# dsd_badge.net
KiCad netlist of a schematic drawn in Altium Designer
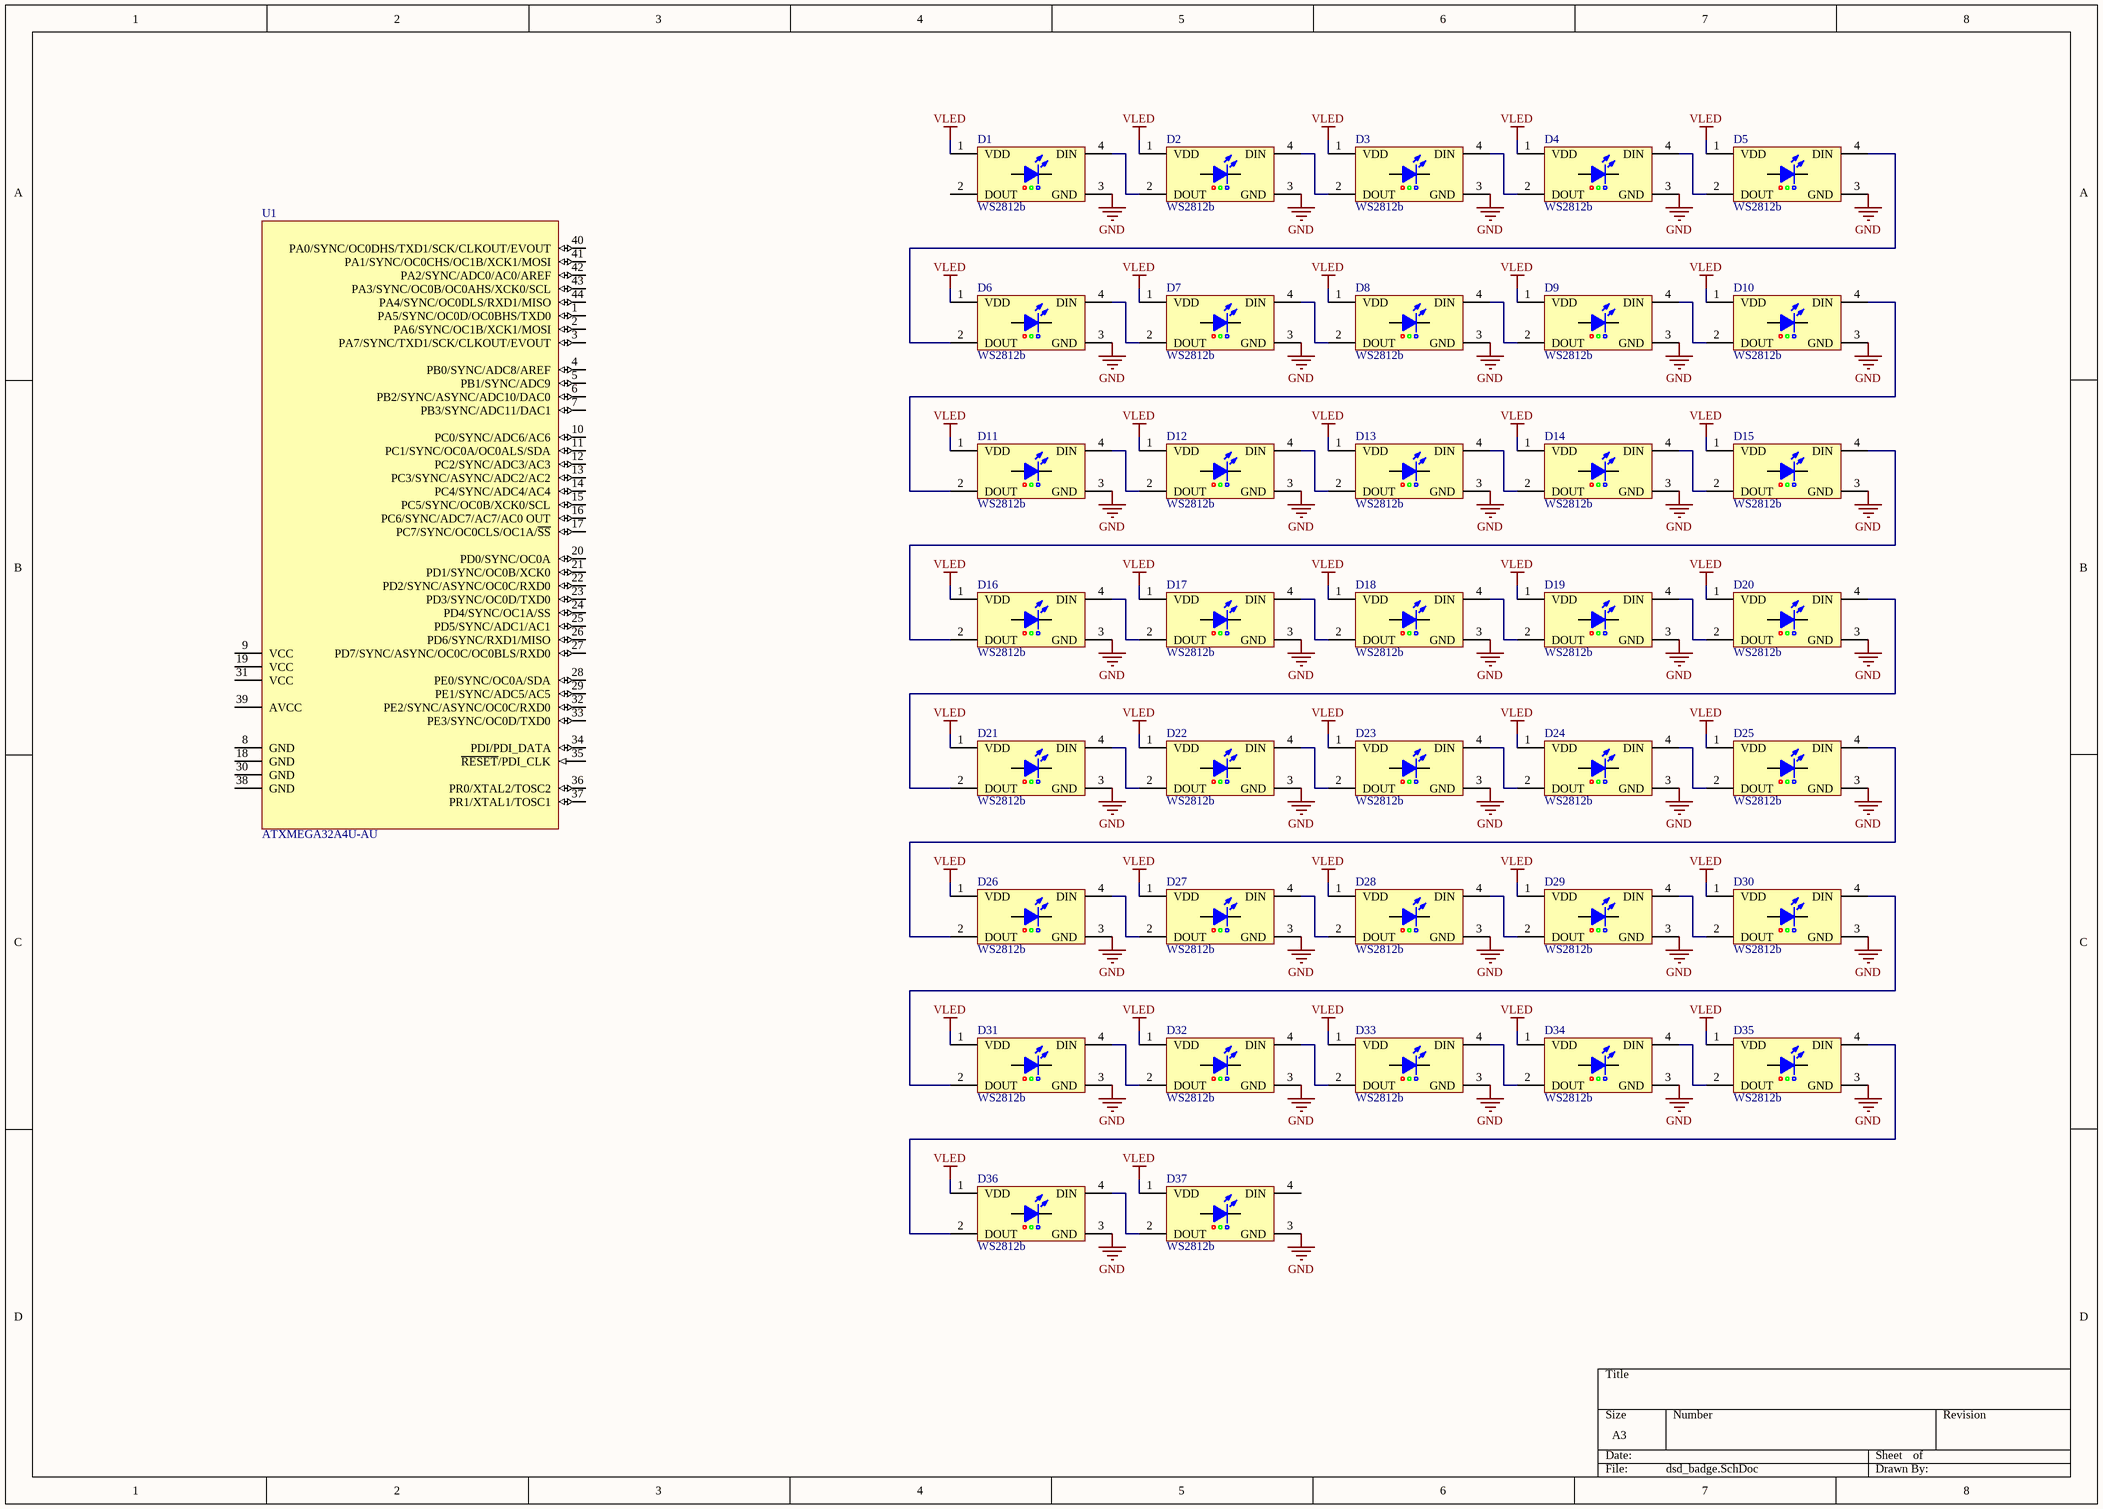
[diagram p0: dsd_badge.SchDoc]

(export (version "E")
  (design (tool "Eeschema 10.0.6"))
  (components
    (comp (ref "D1")
      (value "WS2812b")
      (footprint "WS2812B")
      (description "ADDRESS LED DISCR SER RGB 1=10")
      (fields
        (field (name "MANUFACTURER") "Adafruit Industries")
        (field (name "MANUFACTURER PART NUMBER") "1655")
      )
      (libsource (lib "General") (part "WS2812b"))
    )
    (comp (ref "D2")
      (value "WS2812b")
      (footprint "WS2812B")
      (description "ADDRESS LED DISCR SER RGB 1=10")
      (fields
        (field (name "MANUFACTURER") "Adafruit Industries")
        (field (name "MANUFACTURER PART NUMBER") "1655")
      )
      (libsource (lib "General") (part "WS2812b"))
    )
    (comp (ref "D3")
      (value "WS2812b")
      (footprint "WS2812B")
      (description "ADDRESS LED DISCR SER RGB 1=10")
      (fields
        (field (name "MANUFACTURER") "Adafruit Industries")
        (field (name "MANUFACTURER PART NUMBER") "1655")
      )
      (libsource (lib "General") (part "WS2812b"))
    )
    (comp (ref "D4")
      (value "WS2812b")
      (footprint "WS2812B")
      (description "ADDRESS LED DISCR SER RGB 1=10")
      (fields
        (field (name "MANUFACTURER") "Adafruit Industries")
        (field (name "MANUFACTURER PART NUMBER") "1655")
      )
      (libsource (lib "General") (part "WS2812b"))
    )
    (comp (ref "D5")
      (value "WS2812b")
      (footprint "WS2812B")
      (description "ADDRESS LED DISCR SER RGB 1=10")
      (fields
        (field (name "MANUFACTURER") "Adafruit Industries")
        (field (name "MANUFACTURER PART NUMBER") "1655")
      )
      (libsource (lib "General") (part "WS2812b"))
    )
    (comp (ref "D6")
      (value "WS2812b")
      (footprint "WS2812B")
      (description "ADDRESS LED DISCR SER RGB 1=10")
      (fields
        (field (name "MANUFACTURER") "Adafruit Industries")
        (field (name "MANUFACTURER PART NUMBER") "1655")
      )
      (libsource (lib "General") (part "WS2812b"))
    )
    (comp (ref "D7")
      (value "WS2812b")
      (footprint "WS2812B")
      (description "ADDRESS LED DISCR SER RGB 1=10")
      (fields
        (field (name "MANUFACTURER") "Adafruit Industries")
        (field (name "MANUFACTURER PART NUMBER") "1655")
      )
      (libsource (lib "General") (part "WS2812b"))
    )
    (comp (ref "D8")
      (value "WS2812b")
      (footprint "WS2812B")
      (description "ADDRESS LED DISCR SER RGB 1=10")
      (fields
        (field (name "MANUFACTURER") "Adafruit Industries")
        (field (name "MANUFACTURER PART NUMBER") "1655")
      )
      (libsource (lib "General") (part "WS2812b"))
    )
    (comp (ref "D9")
      (value "WS2812b")
      (footprint "WS2812B")
      (description "ADDRESS LED DISCR SER RGB 1=10")
      (fields
        (field (name "MANUFACTURER") "Adafruit Industries")
        (field (name "MANUFACTURER PART NUMBER") "1655")
      )
      (libsource (lib "General") (part "WS2812b"))
    )
    (comp (ref "D10")
      (value "WS2812b")
      (footprint "WS2812B")
      (description "ADDRESS LED DISCR SER RGB 1=10")
      (fields
        (field (name "MANUFACTURER") "Adafruit Industries")
        (field (name "MANUFACTURER PART NUMBER") "1655")
      )
      (libsource (lib "General") (part "WS2812b"))
    )
    (comp (ref "D11")
      (value "WS2812b")
      (footprint "WS2812B")
      (description "ADDRESS LED DISCR SER RGB 1=10")
      (fields
        (field (name "MANUFACTURER") "Adafruit Industries")
        (field (name "MANUFACTURER PART NUMBER") "1655")
      )
      (libsource (lib "General") (part "WS2812b"))
    )
    (comp (ref "D12")
      (value "WS2812b")
      (footprint "WS2812B")
      (description "ADDRESS LED DISCR SER RGB 1=10")
      (fields
        (field (name "MANUFACTURER") "Adafruit Industries")
        (field (name "MANUFACTURER PART NUMBER") "1655")
      )
      (libsource (lib "General") (part "WS2812b"))
    )
    (comp (ref "D13")
      (value "WS2812b")
      (footprint "WS2812B")
      (description "ADDRESS LED DISCR SER RGB 1=10")
      (fields
        (field (name "MANUFACTURER") "Adafruit Industries")
        (field (name "MANUFACTURER PART NUMBER") "1655")
      )
      (libsource (lib "General") (part "WS2812b"))
    )
    (comp (ref "D14")
      (value "WS2812b")
      (footprint "WS2812B")
      (description "ADDRESS LED DISCR SER RGB 1=10")
      (fields
        (field (name "MANUFACTURER") "Adafruit Industries")
        (field (name "MANUFACTURER PART NUMBER") "1655")
      )
      (libsource (lib "General") (part "WS2812b"))
    )
    (comp (ref "D15")
      (value "WS2812b")
      (footprint "WS2812B")
      (description "ADDRESS LED DISCR SER RGB 1=10")
      (fields
        (field (name "MANUFACTURER") "Adafruit Industries")
        (field (name "MANUFACTURER PART NUMBER") "1655")
      )
      (libsource (lib "General") (part "WS2812b"))
    )
    (comp (ref "D16")
      (value "WS2812b")
      (footprint "WS2812B")
      (description "ADDRESS LED DISCR SER RGB 1=10")
      (fields
        (field (name "MANUFACTURER") "Adafruit Industries")
        (field (name "MANUFACTURER PART NUMBER") "1655")
      )
      (libsource (lib "General") (part "WS2812b"))
    )
    (comp (ref "D17")
      (value "WS2812b")
      (footprint "WS2812B")
      (description "ADDRESS LED DISCR SER RGB 1=10")
      (fields
        (field (name "MANUFACTURER") "Adafruit Industries")
        (field (name "MANUFACTURER PART NUMBER") "1655")
      )
      (libsource (lib "General") (part "WS2812b"))
    )
    (comp (ref "D18")
      (value "WS2812b")
      (footprint "WS2812B")
      (description "ADDRESS LED DISCR SER RGB 1=10")
      (fields
        (field (name "MANUFACTURER") "Adafruit Industries")
        (field (name "MANUFACTURER PART NUMBER") "1655")
      )
      (libsource (lib "General") (part "WS2812b"))
    )
    (comp (ref "D19")
      (value "WS2812b")
      (footprint "WS2812B")
      (description "ADDRESS LED DISCR SER RGB 1=10")
      (fields
        (field (name "MANUFACTURER") "Adafruit Industries")
        (field (name "MANUFACTURER PART NUMBER") "1655")
      )
      (libsource (lib "General") (part "WS2812b"))
    )
    (comp (ref "D20")
      (value "WS2812b")
      (footprint "WS2812B")
      (description "ADDRESS LED DISCR SER RGB 1=10")
      (fields
        (field (name "MANUFACTURER") "Adafruit Industries")
        (field (name "MANUFACTURER PART NUMBER") "1655")
      )
      (libsource (lib "General") (part "WS2812b"))
    )
    (comp (ref "D21")
      (value "WS2812b")
      (footprint "WS2812B")
      (description "ADDRESS LED DISCR SER RGB 1=10")
      (fields
        (field (name "MANUFACTURER") "Adafruit Industries")
        (field (name "MANUFACTURER PART NUMBER") "1655")
      )
      (libsource (lib "General") (part "WS2812b"))
    )
    (comp (ref "D22")
      (value "WS2812b")
      (footprint "WS2812B")
      (description "ADDRESS LED DISCR SER RGB 1=10")
      (fields
        (field (name "MANUFACTURER") "Adafruit Industries")
        (field (name "MANUFACTURER PART NUMBER") "1655")
      )
      (libsource (lib "General") (part "WS2812b"))
    )
    (comp (ref "D23")
      (value "WS2812b")
      (footprint "WS2812B")
      (description "ADDRESS LED DISCR SER RGB 1=10")
      (fields
        (field (name "MANUFACTURER") "Adafruit Industries")
        (field (name "MANUFACTURER PART NUMBER") "1655")
      )
      (libsource (lib "General") (part "WS2812b"))
    )
    (comp (ref "D24")
      (value "WS2812b")
      (footprint "WS2812B")
      (description "ADDRESS LED DISCR SER RGB 1=10")
      (fields
        (field (name "MANUFACTURER") "Adafruit Industries")
        (field (name "MANUFACTURER PART NUMBER") "1655")
      )
      (libsource (lib "General") (part "WS2812b"))
    )
    (comp (ref "D25")
      (value "WS2812b")
      (footprint "WS2812B")
      (description "ADDRESS LED DISCR SER RGB 1=10")
      (fields
        (field (name "MANUFACTURER") "Adafruit Industries")
        (field (name "MANUFACTURER PART NUMBER") "1655")
      )
      (libsource (lib "General") (part "WS2812b"))
    )
    (comp (ref "D26")
      (value "WS2812b")
      (footprint "WS2812B")
      (description "ADDRESS LED DISCR SER RGB 1=10")
      (fields
        (field (name "MANUFACTURER") "Adafruit Industries")
        (field (name "MANUFACTURER PART NUMBER") "1655")
      )
      (libsource (lib "General") (part "WS2812b"))
    )
    (comp (ref "D27")
      (value "WS2812b")
      (footprint "WS2812B")
      (description "ADDRESS LED DISCR SER RGB 1=10")
      (fields
        (field (name "MANUFACTURER") "Adafruit Industries")
        (field (name "MANUFACTURER PART NUMBER") "1655")
      )
      (libsource (lib "General") (part "WS2812b"))
    )
    (comp (ref "D28")
      (value "WS2812b")
      (footprint "WS2812B")
      (description "ADDRESS LED DISCR SER RGB 1=10")
      (fields
        (field (name "MANUFACTURER") "Adafruit Industries")
        (field (name "MANUFACTURER PART NUMBER") "1655")
      )
      (libsource (lib "General") (part "WS2812b"))
    )
    (comp (ref "D29")
      (value "WS2812b")
      (footprint "WS2812B")
      (description "ADDRESS LED DISCR SER RGB 1=10")
      (fields
        (field (name "MANUFACTURER") "Adafruit Industries")
        (field (name "MANUFACTURER PART NUMBER") "1655")
      )
      (libsource (lib "General") (part "WS2812b"))
    )
    (comp (ref "D30")
      (value "WS2812b")
      (footprint "WS2812B")
      (description "ADDRESS LED DISCR SER RGB 1=10")
      (fields
        (field (name "MANUFACTURER") "Adafruit Industries")
        (field (name "MANUFACTURER PART NUMBER") "1655")
      )
      (libsource (lib "General") (part "WS2812b"))
    )
    (comp (ref "D31")
      (value "WS2812b")
      (footprint "WS2812B")
      (description "ADDRESS LED DISCR SER RGB 1=10")
      (fields
        (field (name "MANUFACTURER") "Adafruit Industries")
        (field (name "MANUFACTURER PART NUMBER") "1655")
      )
      (libsource (lib "General") (part "WS2812b"))
    )
    (comp (ref "D32")
      (value "WS2812b")
      (footprint "WS2812B")
      (description "ADDRESS LED DISCR SER RGB 1=10")
      (fields
        (field (name "MANUFACTURER") "Adafruit Industries")
        (field (name "MANUFACTURER PART NUMBER") "1655")
      )
      (libsource (lib "General") (part "WS2812b"))
    )
    (comp (ref "D33")
      (value "WS2812b")
      (footprint "WS2812B")
      (description "ADDRESS LED DISCR SER RGB 1=10")
      (fields
        (field (name "MANUFACTURER") "Adafruit Industries")
        (field (name "MANUFACTURER PART NUMBER") "1655")
      )
      (libsource (lib "General") (part "WS2812b"))
    )
    (comp (ref "D34")
      (value "WS2812b")
      (footprint "WS2812B")
      (description "ADDRESS LED DISCR SER RGB 1=10")
      (fields
        (field (name "MANUFACTURER") "Adafruit Industries")
        (field (name "MANUFACTURER PART NUMBER") "1655")
      )
      (libsource (lib "General") (part "WS2812b"))
    )
    (comp (ref "D35")
      (value "WS2812b")
      (footprint "WS2812B")
      (description "ADDRESS LED DISCR SER RGB 1=10")
      (fields
        (field (name "MANUFACTURER") "Adafruit Industries")
        (field (name "MANUFACTURER PART NUMBER") "1655")
      )
      (libsource (lib "General") (part "WS2812b"))
    )
    (comp (ref "D36")
      (value "WS2812b")
      (footprint "WS2812B")
      (description "ADDRESS LED DISCR SER RGB 1=10")
      (fields
        (field (name "MANUFACTURER") "Adafruit Industries")
        (field (name "MANUFACTURER PART NUMBER") "1655")
      )
      (libsource (lib "General") (part "WS2812b"))
    )
    (comp (ref "D37")
      (value "WS2812b")
      (footprint "WS2812B")
      (description "ADDRESS LED DISCR SER RGB 1=10")
      (fields
        (field (name "MANUFACTURER") "Adafruit Industries")
        (field (name "MANUFACTURER PART NUMBER") "1655")
      )
      (libsource (lib "General") (part "WS2812b"))
    )
    (comp (ref "U1")
      (value "ATXMEGA32A4U-AU")
      (footprint "44A_L")
      (description "IC MCU 8BIT 32KB FLASH 44TQFP")
      (fields (field (name "MANUFACTURER") "Atmel"))
      (libsource (lib "General") (part "ATXMEGA32A4U-AU"))
    )
  )
  (nets
    (net (code "1") (name "GND") (class "Default")
      (node (ref "D1") (pin "3") (pinfunction "GND_3") (pintype "passive"))
      (node (ref "D10") (pin "3") (pinfunction "GND_3") (pintype "passive"))
      (node (ref "D11") (pin "3") (pinfunction "GND_3") (pintype "passive"))
      (node (ref "D12") (pin "3") (pinfunction "GND_3") (pintype "passive"))
      (node (ref "D13") (pin "3") (pinfunction "GND_3") (pintype "passive"))
      (node (ref "D14") (pin "3") (pinfunction "GND_3") (pintype "passive"))
      (node (ref "D15") (pin "3") (pinfunction "GND_3") (pintype "passive"))
      (node (ref "D16") (pin "3") (pinfunction "GND_3") (pintype "passive"))
      (node (ref "D17") (pin "3") (pinfunction "GND_3") (pintype "passive"))
      (node (ref "D18") (pin "3") (pinfunction "GND_3") (pintype "passive"))
      (node (ref "D19") (pin "3") (pinfunction "GND_3") (pintype "passive"))
      (node (ref "D2") (pin "3") (pinfunction "GND_3") (pintype "passive"))
      (node (ref "D20") (pin "3") (pinfunction "GND_3") (pintype "passive"))
      (node (ref "D21") (pin "3") (pinfunction "GND_3") (pintype "passive"))
      (node (ref "D22") (pin "3") (pinfunction "GND_3") (pintype "passive"))
      (node (ref "D23") (pin "3") (pinfunction "GND_3") (pintype "passive"))
      (node (ref "D24") (pin "3") (pinfunction "GND_3") (pintype "passive"))
      (node (ref "D25") (pin "3") (pinfunction "GND_3") (pintype "passive"))
      (node (ref "D26") (pin "3") (pinfunction "GND_3") (pintype "passive"))
      (node (ref "D27") (pin "3") (pinfunction "GND_3") (pintype "passive"))
      (node (ref "D28") (pin "3") (pinfunction "GND_3") (pintype "passive"))
      (node (ref "D29") (pin "3") (pinfunction "GND_3") (pintype "passive"))
      (node (ref "D3") (pin "3") (pinfunction "GND_3") (pintype "passive"))
      (node (ref "D30") (pin "3") (pinfunction "GND_3") (pintype "passive"))
      (node (ref "D31") (pin "3") (pinfunction "GND_3") (pintype "passive"))
      (node (ref "D32") (pin "3") (pinfunction "GND_3") (pintype "passive"))
      (node (ref "D33") (pin "3") (pinfunction "GND_3") (pintype "passive"))
      (node (ref "D34") (pin "3") (pinfunction "GND_3") (pintype "passive"))
      (node (ref "D35") (pin "3") (pinfunction "GND_3") (pintype "passive"))
      (node (ref "D36") (pin "3") (pinfunction "GND_3") (pintype "passive"))
      (node (ref "D37") (pin "3") (pinfunction "GND_3") (pintype "passive"))
      (node (ref "D4") (pin "3") (pinfunction "GND_3") (pintype "passive"))
      (node (ref "D5") (pin "3") (pinfunction "GND_3") (pintype "passive"))
      (node (ref "D6") (pin "3") (pinfunction "GND_3") (pintype "passive"))
      (node (ref "D7") (pin "3") (pinfunction "GND_3") (pintype "passive"))
      (node (ref "D8") (pin "3") (pinfunction "GND_3") (pintype "passive"))
      (node (ref "D9") (pin "3") (pinfunction "GND_3") (pintype "passive"))
    )
    (net (code "2") (name "Net-(D1-DIN)") (class "Default")
      (node (ref "D1") (pin "4") (pinfunction "DIN_4") (pintype "passive"))
      (node (ref "D2") (pin "2") (pinfunction "DOUT_2") (pintype "passive"))
    )
    (net (code "3") (name "Net-(D2-DIN)") (class "Default")
      (node (ref "D2") (pin "4") (pinfunction "DIN_4") (pintype "passive"))
      (node (ref "D3") (pin "2") (pinfunction "DOUT_2") (pintype "passive"))
    )
    (net (code "4") (name "Net-(D3-DIN)") (class "Default")
      (node (ref "D3") (pin "4") (pinfunction "DIN_4") (pintype "passive"))
      (node (ref "D4") (pin "2") (pinfunction "DOUT_2") (pintype "passive"))
    )
    (net (code "5") (name "Net-(D4-DIN)") (class "Default")
      (node (ref "D4") (pin "4") (pinfunction "DIN_4") (pintype "passive"))
      (node (ref "D5") (pin "2") (pinfunction "DOUT_2") (pintype "passive"))
    )
    (net (code "6") (name "Net-(D5-DIN)") (class "Default")
      (node (ref "D5") (pin "4") (pinfunction "DIN_4") (pintype "passive"))
      (node (ref "D6") (pin "2") (pinfunction "DOUT_2") (pintype "passive"))
    )
    (net (code "7") (name "Net-(D6-DIN)") (class "Default")
      (node (ref "D6") (pin "4") (pinfunction "DIN_4") (pintype "passive"))
      (node (ref "D7") (pin "2") (pinfunction "DOUT_2") (pintype "passive"))
    )
    (net (code "8") (name "Net-(D7-DIN)") (class "Default")
      (node (ref "D7") (pin "4") (pinfunction "DIN_4") (pintype "passive"))
      (node (ref "D8") (pin "2") (pinfunction "DOUT_2") (pintype "passive"))
    )
    (net (code "9") (name "Net-(D8-DIN)") (class "Default")
      (node (ref "D8") (pin "4") (pinfunction "DIN_4") (pintype "passive"))
      (node (ref "D9") (pin "2") (pinfunction "DOUT_2") (pintype "passive"))
    )
    (net (code "10") (name "Net-(D10-DIN)") (class "Default")
      (node (ref "D10") (pin "4") (pinfunction "DIN_4") (pintype "passive"))
      (node (ref "D11") (pin "2") (pinfunction "DOUT_2") (pintype "passive"))
    )
    (net (code "11") (name "Net-(D10-DOUT)") (class "Default")
      (node (ref "D10") (pin "2") (pinfunction "DOUT_2") (pintype "passive"))
      (node (ref "D9") (pin "4") (pinfunction "DIN_4") (pintype "passive"))
    )
    (net (code "12") (name "Net-(D11-DIN)") (class "Default")
      (node (ref "D11") (pin "4") (pinfunction "DIN_4") (pintype "passive"))
      (node (ref "D12") (pin "2") (pinfunction "DOUT_2") (pintype "passive"))
    )
    (net (code "13") (name "Net-(D12-DIN)") (class "Default")
      (node (ref "D12") (pin "4") (pinfunction "DIN_4") (pintype "passive"))
      (node (ref "D13") (pin "2") (pinfunction "DOUT_2") (pintype "passive"))
    )
    (net (code "14") (name "Net-(D13-DIN)") (class "Default")
      (node (ref "D13") (pin "4") (pinfunction "DIN_4") (pintype "passive"))
      (node (ref "D14") (pin "2") (pinfunction "DOUT_2") (pintype "passive"))
    )
    (net (code "15") (name "Net-(D14-DIN)") (class "Default")
      (node (ref "D14") (pin "4") (pinfunction "DIN_4") (pintype "passive"))
      (node (ref "D15") (pin "2") (pinfunction "DOUT_2") (pintype "passive"))
    )
    (net (code "16") (name "Net-(D15-DIN)") (class "Default")
      (node (ref "D15") (pin "4") (pinfunction "DIN_4") (pintype "passive"))
      (node (ref "D16") (pin "2") (pinfunction "DOUT_2") (pintype "passive"))
    )
    (net (code "17") (name "Net-(D16-DIN)") (class "Default")
      (node (ref "D16") (pin "4") (pinfunction "DIN_4") (pintype "passive"))
      (node (ref "D17") (pin "2") (pinfunction "DOUT_2") (pintype "passive"))
    )
    (net (code "18") (name "Net-(D17-DIN)") (class "Default")
      (node (ref "D17") (pin "4") (pinfunction "DIN_4") (pintype "passive"))
      (node (ref "D18") (pin "2") (pinfunction "DOUT_2") (pintype "passive"))
    )
    (net (code "19") (name "Net-(D18-DIN)") (class "Default")
      (node (ref "D18") (pin "4") (pinfunction "DIN_4") (pintype "passive"))
      (node (ref "D19") (pin "2") (pinfunction "DOUT_2") (pintype "passive"))
    )
    (net (code "20") (name "Net-(D19-DIN)") (class "Default")
      (node (ref "D19") (pin "4") (pinfunction "DIN_4") (pintype "passive"))
      (node (ref "D20") (pin "2") (pinfunction "DOUT_2") (pintype "passive"))
    )
    (net (code "21") (name "Net-(D20-DIN)") (class "Default")
      (node (ref "D20") (pin "4") (pinfunction "DIN_4") (pintype "passive"))
      (node (ref "D21") (pin "2") (pinfunction "DOUT_2") (pintype "passive"))
    )
    (net (code "22") (name "Net-(D21-DIN)") (class "Default")
      (node (ref "D21") (pin "4") (pinfunction "DIN_4") (pintype "passive"))
      (node (ref "D22") (pin "2") (pinfunction "DOUT_2") (pintype "passive"))
    )
    (net (code "23") (name "Net-(D22-DIN)") (class "Default")
      (node (ref "D22") (pin "4") (pinfunction "DIN_4") (pintype "passive"))
      (node (ref "D23") (pin "2") (pinfunction "DOUT_2") (pintype "passive"))
    )
    (net (code "24") (name "Net-(D23-DIN)") (class "Default")
      (node (ref "D23") (pin "4") (pinfunction "DIN_4") (pintype "passive"))
      (node (ref "D24") (pin "2") (pinfunction "DOUT_2") (pintype "passive"))
    )
    (net (code "25") (name "Net-(D24-DIN)") (class "Default")
      (node (ref "D24") (pin "4") (pinfunction "DIN_4") (pintype "passive"))
      (node (ref "D25") (pin "2") (pinfunction "DOUT_2") (pintype "passive"))
    )
    (net (code "26") (name "Net-(D25-DIN)") (class "Default")
      (node (ref "D25") (pin "4") (pinfunction "DIN_4") (pintype "passive"))
      (node (ref "D26") (pin "2") (pinfunction "DOUT_2") (pintype "passive"))
    )
    (net (code "27") (name "Net-(D26-DIN)") (class "Default")
      (node (ref "D26") (pin "4") (pinfunction "DIN_4") (pintype "passive"))
      (node (ref "D27") (pin "2") (pinfunction "DOUT_2") (pintype "passive"))
    )
    (net (code "28") (name "Net-(D27-DIN)") (class "Default")
      (node (ref "D27") (pin "4") (pinfunction "DIN_4") (pintype "passive"))
      (node (ref "D28") (pin "2") (pinfunction "DOUT_2") (pintype "passive"))
    )
    (net (code "29") (name "Net-(D28-DIN)") (class "Default")
      (node (ref "D28") (pin "4") (pinfunction "DIN_4") (pintype "passive"))
      (node (ref "D29") (pin "2") (pinfunction "DOUT_2") (pintype "passive"))
    )
    (net (code "30") (name "Net-(D29-DIN)") (class "Default")
      (node (ref "D29") (pin "4") (pinfunction "DIN_4") (pintype "passive"))
      (node (ref "D30") (pin "2") (pinfunction "DOUT_2") (pintype "passive"))
    )
    (net (code "31") (name "Net-(D30-DIN)") (class "Default")
      (node (ref "D30") (pin "4") (pinfunction "DIN_4") (pintype "passive"))
      (node (ref "D31") (pin "2") (pinfunction "DOUT_2") (pintype "passive"))
    )
    (net (code "32") (name "Net-(D31-DIN)") (class "Default")
      (node (ref "D31") (pin "4") (pinfunction "DIN_4") (pintype "passive"))
      (node (ref "D32") (pin "2") (pinfunction "DOUT_2") (pintype "passive"))
    )
    (net (code "33") (name "Net-(D32-DIN)") (class "Default")
      (node (ref "D32") (pin "4") (pinfunction "DIN_4") (pintype "passive"))
      (node (ref "D33") (pin "2") (pinfunction "DOUT_2") (pintype "passive"))
    )
    (net (code "34") (name "Net-(D33-DIN)") (class "Default")
      (node (ref "D33") (pin "4") (pinfunction "DIN_4") (pintype "passive"))
      (node (ref "D34") (pin "2") (pinfunction "DOUT_2") (pintype "passive"))
    )
    (net (code "35") (name "Net-(D34-DIN)") (class "Default")
      (node (ref "D34") (pin "4") (pinfunction "DIN_4") (pintype "passive"))
      (node (ref "D35") (pin "2") (pinfunction "DOUT_2") (pintype "passive"))
    )
    (net (code "36") (name "Net-(D35-DIN)") (class "Default")
      (node (ref "D35") (pin "4") (pinfunction "DIN_4") (pintype "passive"))
      (node (ref "D36") (pin "2") (pinfunction "DOUT_2") (pintype "passive"))
    )
    (net (code "37") (name "Net-(D36-DIN)") (class "Default")
      (node (ref "D36") (pin "4") (pinfunction "DIN_4") (pintype "passive"))
      (node (ref "D37") (pin "2") (pinfunction "DOUT_2") (pintype "passive"))
    )
    (net (code "38") (name "VLED") (class "Default")
      (node (ref "D1") (pin "1") (pinfunction "VDD_1") (pintype "passive"))
      (node (ref "D10") (pin "1") (pinfunction "VDD_1") (pintype "passive"))
      (node (ref "D11") (pin "1") (pinfunction "VDD_1") (pintype "passive"))
      (node (ref "D12") (pin "1") (pinfunction "VDD_1") (pintype "passive"))
      (node (ref "D13") (pin "1") (pinfunction "VDD_1") (pintype "passive"))
      (node (ref "D14") (pin "1") (pinfunction "VDD_1") (pintype "passive"))
      (node (ref "D15") (pin "1") (pinfunction "VDD_1") (pintype "passive"))
      (node (ref "D16") (pin "1") (pinfunction "VDD_1") (pintype "passive"))
      (node (ref "D17") (pin "1") (pinfunction "VDD_1") (pintype "passive"))
      (node (ref "D18") (pin "1") (pinfunction "VDD_1") (pintype "passive"))
      (node (ref "D19") (pin "1") (pinfunction "VDD_1") (pintype "passive"))
      (node (ref "D2") (pin "1") (pinfunction "VDD_1") (pintype "passive"))
      (node (ref "D20") (pin "1") (pinfunction "VDD_1") (pintype "passive"))
      (node (ref "D21") (pin "1") (pinfunction "VDD_1") (pintype "passive"))
      (node (ref "D22") (pin "1") (pinfunction "VDD_1") (pintype "passive"))
      (node (ref "D23") (pin "1") (pinfunction "VDD_1") (pintype "passive"))
      (node (ref "D24") (pin "1") (pinfunction "VDD_1") (pintype "passive"))
      (node (ref "D25") (pin "1") (pinfunction "VDD_1") (pintype "passive"))
      (node (ref "D26") (pin "1") (pinfunction "VDD_1") (pintype "passive"))
      (node (ref "D27") (pin "1") (pinfunction "VDD_1") (pintype "passive"))
      (node (ref "D28") (pin "1") (pinfunction "VDD_1") (pintype "passive"))
      (node (ref "D29") (pin "1") (pinfunction "VDD_1") (pintype "passive"))
      (node (ref "D3") (pin "1") (pinfunction "VDD_1") (pintype "passive"))
      (node (ref "D30") (pin "1") (pinfunction "VDD_1") (pintype "passive"))
      (node (ref "D31") (pin "1") (pinfunction "VDD_1") (pintype "passive"))
      (node (ref "D32") (pin "1") (pinfunction "VDD_1") (pintype "passive"))
      (node (ref "D33") (pin "1") (pinfunction "VDD_1") (pintype "passive"))
      (node (ref "D34") (pin "1") (pinfunction "VDD_1") (pintype "passive"))
      (node (ref "D35") (pin "1") (pinfunction "VDD_1") (pintype "passive"))
      (node (ref "D36") (pin "1") (pinfunction "VDD_1") (pintype "passive"))
      (node (ref "D37") (pin "1") (pinfunction "VDD_1") (pintype "passive"))
      (node (ref "D4") (pin "1") (pinfunction "VDD_1") (pintype "passive"))
      (node (ref "D5") (pin "1") (pinfunction "VDD_1") (pintype "passive"))
      (node (ref "D6") (pin "1") (pinfunction "VDD_1") (pintype "passive"))
      (node (ref "D7") (pin "1") (pinfunction "VDD_1") (pintype "passive"))
      (node (ref "D8") (pin "1") (pinfunction "VDD_1") (pintype "passive"))
      (node (ref "D9") (pin "1") (pinfunction "VDD_1") (pintype "passive"))
    )
    (net (code "39") (name "unconnected-(D1-DOUT-Pad2)") (class "Default")
      (node (ref "D1") (pin "2") (pinfunction "DOUT_2") (pintype "passive"))
    )
    (net (code "40") (name "unconnected-(D37-DIN-Pad4)") (class "Default")
      (node (ref "D37") (pin "4") (pinfunction "DIN_4") (pintype "passive"))
    )
    (net (code "41") (name "unconnected-(U1-AVCC-Pad39)") (class "Default")
      (node (ref "U1") (pin "39") (pinfunction "AVCC_39") (pintype "power_in"))
    )
    (net (code "42") (name "unconnected-(U1-GND-Pad8)") (class "Default")
      (node (ref "U1") (pin "8") (pinfunction "GND_8") (pintype "power_in"))
    )
    (net (code "43") (name "unconnected-(U1-GND-Pad18)") (class "Default")
      (node (ref "U1") (pin "18") (pinfunction "GND_18") (pintype "power_in"))
    )
    (net (code "44") (name "unconnected-(U1-GND-Pad30)") (class "Default")
      (node (ref "U1") (pin "30") (pinfunction "GND_30") (pintype "power_in"))
    )
    (net (code "45") (name "unconnected-(U1-GND-Pad38)") (class "Default")
      (node (ref "U1") (pin "38") (pinfunction "GND_38") (pintype "power_in"))
    )
    (net (code "46") (name "unconnected-(U1-PA0{slash}SYNC{slash}OC0DHS{slash}TXD1{slash}SCK{slash}CLKOUT{slash}EVOUT-Pad40)") (class "Default")
      (node (ref "U1") (pin "40") (pinfunction "PA0/SYNC/OC0DHS/TXD1/SCK/CLKOUT/EVOUT_40") (pintype "bidirectional"))
    )
    (net (code "47") (name "unconnected-(U1-PA1{slash}SYNC{slash}OC0CHS{slash}OC1B{slash}XCK1{slash}MOSI-Pad41)") (class "Default")
      (node (ref "U1") (pin "41") (pinfunction "PA1/SYNC/OC0CHS/OC1B/XCK1/MOSI_41") (pintype "bidirectional"))
    )
    (net (code "48") (name "unconnected-(U1-PA2{slash}SYNC{slash}ADC0{slash}AC0{slash}AREF-Pad42)") (class "Default")
      (node (ref "U1") (pin "42") (pinfunction "PA2/SYNC/ADC0/AC0/AREF_42") (pintype "bidirectional"))
    )
    (net (code "49") (name "unconnected-(U1-PA3{slash}SYNC{slash}OC0B{slash}OC0AHS{slash}XCK0{slash}SCL-Pad43)") (class "Default")
      (node (ref "U1") (pin "43") (pinfunction "PA3/SYNC/OC0B/OC0AHS/XCK0/SCL_43") (pintype "bidirectional"))
    )
    (net (code "50") (name "unconnected-(U1-PA4{slash}SYNC{slash}OC0DLS{slash}RXD1{slash}MISO-Pad44)") (class "Default")
      (node (ref "U1") (pin "44") (pinfunction "PA4/SYNC/OC0DLS/RXD1/MISO_44") (pintype "bidirectional"))
    )
    (net (code "51") (name "unconnected-(U1-PA5{slash}SYNC{slash}OC0D{slash}OC0BHS{slash}TXD0-Pad1)") (class "Default")
      (node (ref "U1") (pin "1") (pinfunction "PA5/SYNC/OC0D/OC0BHS/TXD0_1") (pintype "bidirectional"))
    )
    (net (code "52") (name "unconnected-(U1-PA6{slash}SYNC{slash}OC1B{slash}XCK1{slash}MOSI-Pad2)") (class "Default")
      (node (ref "U1") (pin "2") (pinfunction "PA6/SYNC/OC1B/XCK1/MOSI_2") (pintype "bidirectional"))
    )
    (net (code "53") (name "unconnected-(U1-PA7{slash}SYNC{slash}TXD1{slash}SCK{slash}CLKOUT{slash}EVOUT-Pad3)") (class "Default")
      (node (ref "U1") (pin "3") (pinfunction "PA7/SYNC/TXD1/SCK/CLKOUT/EVOUT_3") (pintype "bidirectional"))
    )
    (net (code "54") (name "unconnected-(U1-PB0{slash}SYNC{slash}ADC8{slash}AREF-Pad4)") (class "Default")
      (node (ref "U1") (pin "4") (pinfunction "PB0/SYNC/ADC8/AREF_4") (pintype "bidirectional"))
    )
    (net (code "55") (name "unconnected-(U1-PB1{slash}SYNC{slash}ADC9-Pad5)") (class "Default")
      (node (ref "U1") (pin "5") (pinfunction "PB1/SYNC/ADC9_5") (pintype "bidirectional"))
    )
    (net (code "56") (name "unconnected-(U1-PB2{slash}SYNC{slash}ASYNC{slash}ADC10{slash}DAC0-Pad6)") (class "Default")
      (node (ref "U1") (pin "6") (pinfunction "PB2/SYNC/ASYNC/ADC10/DAC0_6") (pintype "bidirectional"))
    )
    (net (code "57") (name "unconnected-(U1-PB3{slash}SYNC{slash}ADC11{slash}DAC1-Pad7)") (class "Default")
      (node (ref "U1") (pin "7") (pinfunction "PB3/SYNC/ADC11/DAC1_7") (pintype "bidirectional"))
    )
    (net (code "58") (name "unconnected-(U1-PC0{slash}SYNC{slash}ADC6{slash}AC6-Pad10)") (class "Default")
      (node (ref "U1") (pin "10") (pinfunction "PC0/SYNC/ADC6/AC6_10") (pintype "bidirectional"))
    )
    (net (code "59") (name "unconnected-(U1-PC1{slash}SYNC{slash}OC0A{slash}OC0ALS{slash}SDA-Pad11)") (class "Default")
      (node (ref "U1") (pin "11") (pinfunction "PC1/SYNC/OC0A/OC0ALS/SDA_11") (pintype "bidirectional"))
    )
    (net (code "60") (name "unconnected-(U1-PC2{slash}SYNC{slash}ADC3{slash}AC3-Pad12)") (class "Default")
      (node (ref "U1") (pin "12") (pinfunction "PC2/SYNC/ADC3/AC3_12") (pintype "bidirectional"))
    )
    (net (code "61") (name "unconnected-(U1-PC3{slash}SYNC{slash}ASYNC{slash}ADC2{slash}AC2-Pad13)") (class "Default")
      (node (ref "U1") (pin "13") (pinfunction "PC3/SYNC/ASYNC/ADC2/AC2_13") (pintype "bidirectional"))
    )
    (net (code "62") (name "unconnected-(U1-PC4{slash}SYNC{slash}ADC4{slash}AC4-Pad14)") (class "Default")
      (node (ref "U1") (pin "14") (pinfunction "PC4/SYNC/ADC4/AC4_14") (pintype "bidirectional"))
    )
    (net (code "63") (name "unconnected-(U1-PC5{slash}SYNC{slash}OC0B{slash}XCK0{slash}SCL-Pad15)") (class "Default")
      (node (ref "U1") (pin "15") (pinfunction "PC5/SYNC/OC0B/XCK0/SCL_15") (pintype "bidirectional"))
    )
    (net (code "64") (name "unconnected-(U1-PC6{slash}SYNC{slash}ADC7{slash}AC7{slash}AC0_OUT-Pad16)") (class "Default")
      (node (ref "U1") (pin "16") (pinfunction "PC6/SYNC/ADC7/AC7/AC0_OUT_16") (pintype "bidirectional"))
    )
    (net (code "65") (name "unconnected-(U1-PC7{slash}SYNC{slash}OC0CLS{slash}OC1A{slash}~{SS}-Pad17)") (class "Default")
      (node (ref "U1") (pin "17") (pinfunction "PC7/SYNC/OC0CLS/OC1A/~{SS}_17") (pintype "bidirectional"))
    )
    (net (code "66") (name "unconnected-(U1-PD0{slash}SYNC{slash}OC0A-Pad20)") (class "Default")
      (node (ref "U1") (pin "20") (pinfunction "PD0/SYNC/OC0A_20") (pintype "bidirectional"))
    )
    (net (code "67") (name "unconnected-(U1-PD1{slash}SYNC{slash}OC0B{slash}XCK0-Pad21)") (class "Default")
      (node (ref "U1") (pin "21") (pinfunction "PD1/SYNC/OC0B/XCK0_21") (pintype "bidirectional"))
    )
    (net (code "68") (name "unconnected-(U1-PD2{slash}SYNC{slash}ASYNC{slash}OC0C{slash}RXD0-Pad22)") (class "Default")
      (node (ref "U1") (pin "22") (pinfunction "PD2/SYNC/ASYNC/OC0C/RXD0_22") (pintype "bidirectional"))
    )
    (net (code "69") (name "unconnected-(U1-PD3{slash}SYNC{slash}OC0D{slash}TXD0-Pad23)") (class "Default")
      (node (ref "U1") (pin "23") (pinfunction "PD3/SYNC/OC0D/TXD0_23") (pintype "bidirectional"))
    )
    (net (code "70") (name "unconnected-(U1-PD4{slash}SYNC{slash}OC1A{slash}SS-Pad24)") (class "Default")
      (node (ref "U1") (pin "24") (pinfunction "PD4/SYNC/OC1A/SS_24") (pintype "bidirectional"))
    )
    (net (code "71") (name "unconnected-(U1-PD5{slash}SYNC{slash}ADC1{slash}AC1-Pad25)") (class "Default")
      (node (ref "U1") (pin "25") (pinfunction "PD5/SYNC/ADC1/AC1_25") (pintype "bidirectional"))
    )
    (net (code "72") (name "unconnected-(U1-PD6{slash}SYNC{slash}RXD1{slash}MISO-Pad26)") (class "Default")
      (node (ref "U1") (pin "26") (pinfunction "PD6/SYNC/RXD1/MISO_26") (pintype "bidirectional"))
    )
    (net (code "73") (name "unconnected-(U1-PD7{slash}SYNC{slash}ASYNC{slash}OC0C{slash}OC0BLS{slash}RXD0-Pad27)") (class "Default")
      (node (ref "U1") (pin "27") (pinfunction "PD7/SYNC/ASYNC/OC0C/OC0BLS/RXD0_27") (pintype "bidirectional"))
    )
    (net (code "74") (name "unconnected-(U1-PDI{slash}PDI_DATA-Pad34)") (class "Default")
      (node (ref "U1") (pin "34") (pinfunction "PDI/PDI_DATA_34") (pintype "bidirectional"))
    )
    (net (code "75") (name "unconnected-(U1-PE0{slash}SYNC{slash}OC0A{slash}SDA-Pad28)") (class "Default")
      (node (ref "U1") (pin "28") (pinfunction "PE0/SYNC/OC0A/SDA_28") (pintype "bidirectional"))
    )
    (net (code "76") (name "unconnected-(U1-PE1{slash}SYNC{slash}ADC5{slash}AC5-Pad29)") (class "Default")
      (node (ref "U1") (pin "29") (pinfunction "PE1/SYNC/ADC5/AC5_29") (pintype "bidirectional"))
    )
    (net (code "77") (name "unconnected-(U1-PE2{slash}SYNC{slash}ASYNC{slash}OC0C{slash}RXD0-Pad32)") (class "Default")
      (node (ref "U1") (pin "32") (pinfunction "PE2/SYNC/ASYNC/OC0C/RXD0_32") (pintype "bidirectional"))
    )
    (net (code "78") (name "unconnected-(U1-PE3{slash}SYNC{slash}OC0D{slash}TXD0-Pad33)") (class "Default")
      (node (ref "U1") (pin "33") (pinfunction "PE3/SYNC/OC0D/TXD0_33") (pintype "bidirectional"))
    )
    (net (code "79") (name "unconnected-(U1-PR0{slash}XTAL2{slash}TOSC2-Pad36)") (class "Default")
      (node (ref "U1") (pin "36") (pinfunction "PR0/XTAL2/TOSC2_36") (pintype "bidirectional"))
    )
    (net (code "80") (name "unconnected-(U1-PR1{slash}XTAL1{slash}TOSC1-Pad37)") (class "Default")
      (node (ref "U1") (pin "37") (pinfunction "PR1/XTAL1/TOSC1_37") (pintype "bidirectional"))
    )
    (net (code "81") (name "unconnected-(U1-VCC-Pad9)") (class "Default")
      (node (ref "U1") (pin "9") (pinfunction "VCC_9") (pintype "power_in"))
    )
    (net (code "82") (name "unconnected-(U1-VCC-Pad19)") (class "Default")
      (node (ref "U1") (pin "19") (pinfunction "VCC_19") (pintype "power_in"))
    )
    (net (code "83") (name "unconnected-(U1-VCC-Pad31)") (class "Default")
      (node (ref "U1") (pin "31") (pinfunction "VCC_31") (pintype "power_in"))
    )
    (net (code "84") (name "unconnected-(U1-~{RESET}{slash}PDI_CLK-Pad35)") (class "Default")
      (node (ref "U1") (pin "35") (pinfunction "~{RESET}/PDI_CLK_35") (pintype "input"))
    )
  )
)
